# SwitchingRegulator.net
KiCad netlist of a schematic drawn in Altium Designer
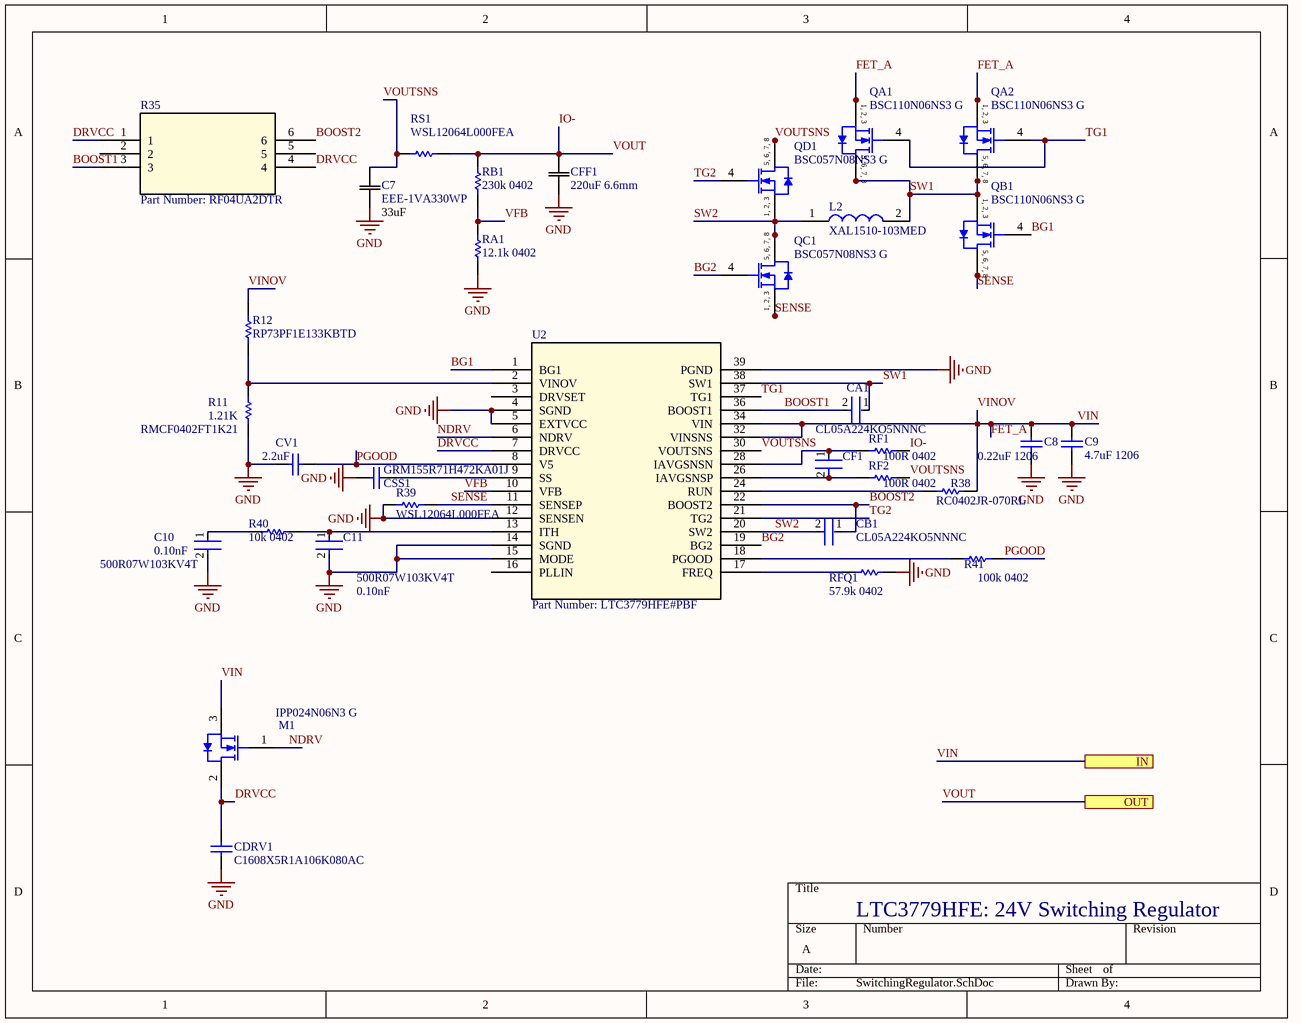
[diagram p0: SwitchingRegulator.SchDoc]

(export (version "E")
  (design (tool "Eeschema 10.0.6"))
  (components
    (comp (ref "C7")
      (value "EEE-1VA330WP")
      (footprint "CAPAE660X800N")
      (description "CAP ALUM 33UF 20% 35V SMD")
      (fields (field (name "ALTIUM_VALUE") "33uF"))
      (libsource (lib "2020-05-16_18-26-28") (part "UCV1V221MCL1GS"))
    )
    (comp (ref "C8")
      (value "0.22uF 1206")
      (footprint "CAPC1608X90X35ML10T15")
      (description "Chip Capacitor, 10 nF, +/- 10%, 50 V, -55 to 125 degC, 0603 (1608 Metric), RoHS, Tape and Reel")
      (fields (field (name "VOLTAGE") "50V") (field (name "TOLERANCE") "10%"))
      (libsource (lib "Altium Content Vault") (part "CAP-NP-2"))
    )
    (comp (ref "C9")
      (value "4.7uF 1206")
      (footprint "CAPC3216X180X50ML20T25")
      (description "Chip Capacitor, 1 uF, +/- 10%, 25 V, -55 to 125 degC, 1206 (3216 Metric), RoHS, Tape and Reel")
      (fields (field (name "MANUFACTURER") "Kemet") (field (name "TOLERANCE") "10%"))
      (libsource (lib "Altium Content Vault") (part "CAP-NP-2"))
    )
    (comp (ref "C10")
      (value "500R07W103KV4T")
      (footprint "FP-GRM15-MFG")
      (description "CAP CER 0.1UF 16V X7R 0402")
      (fields
        (field (name "MANUFACTURER PART NUMBER") "GRM155R71C104KA88D")
        (field (name "TOLERANCE") "10%")
        (field (name "CAPACITANCE") "0.10nF")
      )
      (libsource (lib "Altium Content Vault") (part "236180d848d6139a670b325ea6854c9"))
    )
    (comp (ref "C11")
      (value "500R07W103KV4T")
      (footprint "FP-GRM15-MFG")
      (description "CAP CER 0.1UF 16V X7R 0402")
      (fields
        (field (name "MANUFACTURER PART NUMBER") "GRM155R71C104KA88D")
        (field (name "TOLERANCE") "10%")
        (field (name "CAPACITANCE") "0.10nF")
      )
      (libsource (lib "Altium Content Vault") (part "236180d848d6139a670b325ea6854c9"))
    )
    (comp (ref "CA1")
      (value "CL05A224KO5NNNC")
      (footprint "FP-GRM15-MFG")
      (description "CAP CER 0.22UF 16V X5R 0402")
      (libsource (lib "Miscellaneous Devices") (part "236180d848d6139a670b325ea6854c9"))
    )
    (comp (ref "CB1")
      (value "CL05A224KO5NNNC")
      (footprint "FP-GRM15-MFG")
      (description "CAP CER 0.22UF 16V X5R 0402")
      (libsource (lib "Miscellaneous Devices") (part "236180d848d6139a670b325ea6854c9"))
    )
    (comp (ref "CDRV1")
      (value "C1608X5R1A106K080AC")
      (footprint "CAPC1608X90X20ML10")
      (description "Chip Capacitor, 10 uF, +/- 10%, 10 V, -55 to 85 degC, 0603 (1608 Metric), RoHS, Tape and Reel")
      (fields
        (field (name "PCN PART NUMBER") "MLCCPartNumberChange30/Nov/2012")
        (field (name "TOLERANCE") "±10%")
      )
      (libsource (lib "Altium Content Vault") (part "CAP-NP-2"))
    )
    (comp (ref "CF1")
      (value "C1608X5R1C335K080AC")
      (footprint "FP-GRM15-MFG")
      (description "CAP CER 3.3UF 16V X5R 0603")
      (libsource (lib "Miscellaneous Devices") (part "236180d848d6139a670b325ea6854c9"))
    )
    (comp (ref "CFF1")
      (value "220uF 6.6mm")
      (footprint "CAPAE660X800N")
      (description "No Description Available")
      (fields
        (field (name "MANUFACTURER_PART_NUMBER") "UCV1V221MCL1GS")
        (field (name "COPYRIGHT") "Copyright (C) 2018 Accelerated Designs. All rights reserved")
      )
      (libsource (lib "2020-05-16_18-26-28") (part "UCV1V221MCL1GS"))
    )
    (comp (ref "CSS1")
      (value "GRM155R71H472KA01J")
      (footprint "CAPC1005X55X25NL05T10")
      (description "CAP CER 4700PF 50V X7R 0402")
      (libsource (lib "Miscellaneous Devices") (part "CAP"))
    )
    (comp (ref "CV1")
      (value "2.2uF")
      (footprint "CAPC1005X55X25ML05T10")
      (description "CAP CER 2.2UF 6.3V X5R 0402")
      (fields (field (name "Comment") "GRM155R60J225ME15D"))
      (libsource (lib "Miscellaneous Devices") (part "CAP"))
    )
    (comp (ref "L2")
      (value "XAL1510-103MED")
      (footprint "PDB_footprints:XAL1513153MEB")
      (description "Inductor")
      (fields (field (name "MOUSER PART NUMBER") "994-XAL1510-103MED"))
      (libsource (lib "*") (part "XAL1510-103MED"))
    )
    (comp (ref "M1")
      (value "IPP024N06N3 G")
      (footprint "INF-PG-TO220-3-1_A_V")
      (fields (field (name "MANUFACTURER") "Infineon"))
      (libsource (lib "Altium Content Vault") (part "INF-NEMOS-GDS-3"))
    )
    (comp (ref "QA1")
      (value "BSC110N06NS3 G")
      (footprint "INF-PG-TDSON-8-1_V")
      (fields (field (name "MANUFACTURER") "Infineon"))
      (libsource (lib "Altium Content Vault") (part "INF-NEMOS-SSSGDDDD-8"))
    )
    (comp (ref "QA2")
      (value "BSC110N06NS3 G")
      (footprint "INF-PG-TDSON-8-1_V")
      (fields (field (name "MANUFACTURER") "Infineon"))
      (libsource (lib "Altium Content Vault") (part "INF-NEMOS-SSSGDDDD-8"))
    )
    (comp (ref "QB1")
      (value "BSC110N06NS3 G")
      (footprint "INF-PG-TDSON-8-1_V")
      (fields (field (name "MANUFACTURER") "Infineon"))
      (libsource (lib "Altium Content Vault") (part "INF-NEMOS-SSSGDDDD-8"))
    )
    (comp (ref "QC1")
      (value "BSC057N08NS3 G")
      (footprint "INF-PG-TDSON-8-1_V")
      (fields (field (name "MANUFACTURER") "Infineon"))
      (libsource (lib "Altium Content Vault") (part "INF-NEMOS-SSSGDDDD-8"))
    )
    (comp (ref "QD1")
      (value "BSC057N08NS3 G")
      (footprint "INF-PG-TDSON-8-1_V")
      (fields (field (name "MANUFACTURER") "Infineon"))
      (libsource (lib "Altium Content Vault") (part "INF-NEMOS-SSSGDDDD-8"))
    )
    (comp (ref "R11")
      (value "RMCF0402FT1K21")
      (footprint "RESC1005X40X25NL05T10")
      (description "RES 1.21K OHM 1% 1/16W 0402")
      (fields
        (field (name "MANUFACTURER") "Yageo / Phycomp")
        (field (name "PART NUMBER") "RC0402JR-070RL")
        (field (name "ALTIUM_VALUE") "1.21K")
      )
      (libsource (lib "Altium Content Vault") (part "RES"))
    )
    (comp (ref "R12")
      (value "RP73PF1E133KBTD")
      (footprint "RESC1005X40X25NL05T10")
      (description "RES 133K OHM 0.1% 1/10W 0402")
      (libsource (lib "Miscellaneous Devices") (part "RES"))
    )
    (comp (ref "R35")
      (value "Part Number: RF04UA2DTR")
      (footprint "RF04")
      (description "No Description Available")
      (fields
        (field (name "MANUFACTURER_PART_NUMBER") "RF04UA2DTR")
        (field (name "COPYRIGHT") "Copyright (C) 2018 Accelerated Designs. All rights reserved")
      )
      (libsource (lib "2020-05-23_22-38-39") (part "RF04UA2DTR"))
    )
    (comp (ref "R38")
      (value "RC0402JR-070RL")
      (footprint "RESC1005X40X25NL05T10")
      (fields (field (name "MANUFACTURER") "Yageo / Phycomp"))
      (libsource (lib "Altium Content Vault") (part "RES"))
    )
    (comp (ref "R39")
      (value "WSL12064L000FEA")
      (footprint "RESC3216X89X51LL25T25")
      (description "RES SMD 4mR 1% 1/8W 1206")
      (libsource (lib "Miscellaneous Devices") (part "RES"))
    )
    (comp (ref "R40")
      (value "10k 0402")
      (footprint "RESC1005X40X25NL05T10")
      (fields (field (name "MANUFACTURER") "Yageo / Phycomp") (field (name "PART NUMBER") "RC0402JR-070RL"))
      (libsource (lib "Altium Content Vault") (part "RES"))
    )
    (comp (ref "R41")
      (value "100k 0402")
      (footprint "RESC1005X40X25NL05T10")
      (fields (field (name "MANUFACTURER") "Yageo / Phycomp") (field (name "PART NUMBER") "RC0402JR-070RL"))
      (libsource (lib "Altium Content Vault") (part "RES"))
    )
    (comp (ref "RA1")
      (value "12.1k 0402")
      (footprint "RESC1005X40X25NL05T10")
      (fields (field (name "MANUFACTURER") "Yageo / Phycomp") (field (name "PART NUMBER") "RC0402JR-070RL"))
      (libsource (lib "Altium Content Vault") (part "RES"))
    )
    (comp (ref "RB1")
      (value "230k 0402")
      (footprint "RESC1005X40X25NL05T10")
      (fields (field (name "MANUFACTURER") "Yageo / Phycomp") (field (name "PART NUMBER") "RC0402JR-070RL"))
      (libsource (lib "Altium Content Vault") (part "RES"))
    )
    (comp (ref "RF1")
      (value "100R 0402")
      (footprint "RESC1005X40X25NL05T05")
      (fields (field (name "PART NUMBER") "CRCW0402100RFKED") (field (name "MANUFACTURER") "Vishay Dale"))
      (libsource (lib "Altium Content Vault") (part "RES"))
    )
    (comp (ref "RF2")
      (value "100R 0402")
      (footprint "RESC1005X40X25NL05T05")
      (fields (field (name "PART NUMBER") "CRCW0402100RFKED") (field (name "MANUFACTURER") "Vishay Dale"))
      (libsource (lib "Altium Content Vault") (part "RES"))
    )
    (comp (ref "RFQ1")
      (value "57.9k 0402")
      (footprint "RESC1005X40X25NL05T10")
      (fields (field (name "MANUFACTURER") "Yageo / Phycomp") (field (name "PART NUMBER") "RC0402JR-070RL"))
      (libsource (lib "Altium Content Vault") (part "RES"))
    )
    (comp (ref "RS1")
      (value "WSL12064L000FEA")
      (footprint "RESC3216X89X51LL25T25")
      (description "RES SMD 4mR 1% 1/8W 1206")
      (libsource (lib "Miscellaneous Devices") (part "RES"))
    )
    (comp (ref "U2")
      (value "Part Number: LTC3779HFE#PBF")
      (footprint "SOP50P640X120-39N")
      (description "No Description Available")
      (fields
        (field (name "MANUFACTURER_PART_NUMBER") "LTC3779HFE#PBF")
        (field (name "COPYRIGHT") "Copyright (C) 2016 Accelerated Designs. All rights reserved")
      )
      (libsource (lib "2020-05-16_19-22-25") (part "LTC3779HFE#PBF"))
    )
  )
  (nets
    (net (code "1") (name "/BG1") (class "Default")
      (node (ref "QB1") (pin "4") (pinfunction "GATE_4") (pintype "passive"))
      (node (ref "U2") (pin "1") (pinfunction "BG1_1") (pintype "passive"))
    )
    (net (code "2") (name "/BG2") (class "Default")
      (node (ref "QC1") (pin "4") (pinfunction "GATE_4") (pintype "passive"))
      (node (ref "U2") (pin "19") (pinfunction "BG2_19") (pintype "passive"))
    )
    (net (code "3") (name "/BOOST1") (class "Default")
      (node (ref "CA1") (pin "2") (pinfunction "2_2") (pintype "passive"))
      (node (ref "R35") (pin "3") (pinfunction "3_3") (pintype "passive"))
      (node (ref "U2") (pin "36") (pinfunction "BOOST1_36") (pintype "passive"))
    )
    (net (code "4") (name "/BOOST2") (class "Default")
      (node (ref "CB1") (pin "1") (pinfunction "1_1") (pintype "passive"))
      (node (ref "R35") (pin "6") (pinfunction "6_6") (pintype "passive"))
      (node (ref "U2") (pin "22") (pinfunction "BOOST2_22") (pintype "passive"))
    )
    (net (code "5") (name "/DRVCC") (class "Default")
      (node (ref "CDRV1") (pin "2") (pinfunction "2_2") (pintype "passive"))
      (node (ref "M1") (pin "2") (pinfunction "DRAIN_2") (pintype "passive"))
      (node (ref "R35") (pin "1") (pinfunction "1_1") (pintype "passive"))
      (node (ref "R35") (pin "4") (pinfunction "4_4") (pintype "passive"))
      (node (ref "U2") (pin "7") (pinfunction "DRVCC_7") (pintype "passive"))
    )
    (net (code "6") (name "/FET_A") (class "Default")
      (node (ref "C8") (pin "2") (pinfunction "2_2") (pintype "passive"))
      (node (ref "C9") (pin "2") (pinfunction "2_2") (pintype "passive"))
      (node (ref "M1") (pin "3") (pinfunction "SOURCE_3") (pintype "passive"))
      (node (ref "QA1") (pin "1") (pinfunction "SOURCE_1") (pintype "passive"))
      (node (ref "QA1") (pin "2") (pinfunction "SOURCE_2") (pintype "passive"))
      (node (ref "QA1") (pin "3") (pinfunction "SOURCE_3") (pintype "passive"))
      (node (ref "QA2") (pin "1") (pinfunction "SOURCE_1") (pintype "passive"))
      (node (ref "QA2") (pin "2") (pinfunction "SOURCE_2") (pintype "passive"))
      (node (ref "QA2") (pin "3") (pinfunction "SOURCE_3") (pintype "passive"))
      (node (ref "R12") (pin "1") (pinfunction "1_1") (pintype "passive"))
      (node (ref "R38") (pin "1") (pinfunction "1_1") (pintype "passive"))
      (node (ref "U2") (pin "32") (pinfunction "VINSNS_32") (pintype "passive"))
      (node (ref "U2") (pin "34") (pinfunction "VIN_34") (pintype "passive"))
    )
    (net (code "7") (name "/IO-") (class "Default")
      (node (ref "CFF1") (pin "2") (pinfunction "2_2") (pintype "passive"))
      (node (ref "RB1") (pin "2") (pinfunction "2_2") (pintype "passive"))
      (node (ref "RF1") (pin "2") (pinfunction "2_2") (pintype "passive"))
      (node (ref "RS1") (pin "2") (pinfunction "2_2") (pintype "passive"))
    )
    (net (code "8") (name "/NDRV") (class "Default")
      (node (ref "M1") (pin "1") (pinfunction "GATE_1") (pintype "passive"))
      (node (ref "U2") (pin "6") (pinfunction "NDRV_6") (pintype "passive"))
    )
    (net (code "9") (name "/PGOOD") (class "Default")
      (node (ref "CV1") (pin "2") (pinfunction "2_2") (pintype "passive"))
      (node (ref "R41") (pin "1") (pinfunction "1_1") (pintype "passive"))
      (node (ref "U2") (pin "8") (pinfunction "V5_8") (pintype "passive"))
    )
    (net (code "10") (name "/SENSE") (class "Default")
      (node (ref "QB1") (pin "5") (pinfunction "DRAIN_5") (pintype "passive"))
      (node (ref "QB1") (pin "6") (pinfunction "DRAIN_6") (pintype "passive"))
      (node (ref "QB1") (pin "7") (pinfunction "DRAIN_7") (pintype "passive"))
      (node (ref "QB1") (pin "8") (pinfunction "DRAIN_8") (pintype "passive"))
      (node (ref "QC1") (pin "1") (pinfunction "SOURCE_1") (pintype "passive"))
      (node (ref "QC1") (pin "2") (pinfunction "SOURCE_2") (pintype "passive"))
      (node (ref "QC1") (pin "3") (pinfunction "SOURCE_3") (pintype "passive"))
      (node (ref "R39") (pin "2") (pinfunction "2_2") (pintype "passive"))
      (node (ref "U2") (pin "11") (pinfunction "SENSEP_11") (pintype "passive"))
    )
    (net (code "11") (name "/SW1") (class "Default")
      (node (ref "CA1") (pin "1") (pinfunction "1_1") (pintype "passive"))
      (node (ref "L2") (pin "2") (pinfunction "2_2") (pintype "passive"))
      (node (ref "QA1") (pin "5") (pinfunction "DRAIN_5") (pintype "passive"))
      (node (ref "QA1") (pin "6") (pinfunction "DRAIN_6") (pintype "passive"))
      (node (ref "QA1") (pin "7") (pinfunction "DRAIN_7") (pintype "passive"))
      (node (ref "QA1") (pin "8") (pinfunction "DRAIN_8") (pintype "passive"))
      (node (ref "QA2") (pin "5") (pinfunction "DRAIN_5") (pintype "passive"))
      (node (ref "QA2") (pin "6") (pinfunction "DRAIN_6") (pintype "passive"))
      (node (ref "QA2") (pin "7") (pinfunction "DRAIN_7") (pintype "passive"))
      (node (ref "QA2") (pin "8") (pinfunction "DRAIN_8") (pintype "passive"))
      (node (ref "QB1") (pin "1") (pinfunction "SOURCE_1") (pintype "passive"))
      (node (ref "QB1") (pin "2") (pinfunction "SOURCE_2") (pintype "passive"))
      (node (ref "QB1") (pin "3") (pinfunction "SOURCE_3") (pintype "passive"))
      (node (ref "U2") (pin "38") (pinfunction "SW1_38") (pintype "passive"))
    )
    (net (code "12") (name "/SW2") (class "Default")
      (node (ref "CB1") (pin "2") (pinfunction "2_2") (pintype "passive"))
      (node (ref "L2") (pin "1") (pinfunction "1_1") (pintype "passive"))
      (node (ref "QC1") (pin "5") (pinfunction "DRAIN_5") (pintype "passive"))
      (node (ref "QC1") (pin "6") (pinfunction "DRAIN_6") (pintype "passive"))
      (node (ref "QC1") (pin "7") (pinfunction "DRAIN_7") (pintype "passive"))
      (node (ref "QC1") (pin "8") (pinfunction "DRAIN_8") (pintype "passive"))
      (node (ref "QD1") (pin "1") (pinfunction "SOURCE_1") (pintype "passive"))
      (node (ref "QD1") (pin "2") (pinfunction "SOURCE_2") (pintype "passive"))
      (node (ref "QD1") (pin "3") (pinfunction "SOURCE_3") (pintype "passive"))
      (node (ref "U2") (pin "20") (pinfunction "SW2_20") (pintype "passive"))
    )
    (net (code "13") (name "/TG1") (class "Default")
      (node (ref "QA1") (pin "4") (pinfunction "GATE_4") (pintype "passive"))
      (node (ref "QA2") (pin "4") (pinfunction "GATE_4") (pintype "passive"))
      (node (ref "U2") (pin "37") (pinfunction "TG1_37") (pintype "passive"))
    )
    (net (code "14") (name "/TG2") (class "Default")
      (node (ref "QD1") (pin "4") (pinfunction "GATE_4") (pintype "passive"))
      (node (ref "U2") (pin "21") (pinfunction "TG2_21") (pintype "passive"))
    )
    (net (code "15") (name "/VFB") (class "Default")
      (node (ref "RA1") (pin "2") (pinfunction "2_2") (pintype "passive"))
      (node (ref "RB1") (pin "1") (pinfunction "1_1") (pintype "passive"))
      (node (ref "U2") (pin "10") (pinfunction "VFB_10") (pintype "passive"))
    )
    (net (code "16") (name "/VOUTSNS") (class "Default")
      (node (ref "C7") (pin "2") (pinfunction "2_2") (pintype "passive"))
      (node (ref "QD1") (pin "5") (pinfunction "DRAIN_5") (pintype "passive"))
      (node (ref "QD1") (pin "6") (pinfunction "DRAIN_6") (pintype "passive"))
      (node (ref "QD1") (pin "7") (pinfunction "DRAIN_7") (pintype "passive"))
      (node (ref "QD1") (pin "8") (pinfunction "DRAIN_8") (pintype "passive"))
      (node (ref "RF2") (pin "2") (pinfunction "2_2") (pintype "passive"))
      (node (ref "RS1") (pin "1") (pinfunction "1_1") (pintype "passive"))
      (node (ref "U2") (pin "30") (pinfunction "VOUTSNS_30") (pintype "passive"))
    )
    (net (code "17") (name "GND") (class "Default")
      (node (ref "C10") (pin "2") (pinfunction "2_2") (pintype "passive"))
      (node (ref "C11") (pin "2") (pinfunction "2_2") (pintype "passive"))
      (node (ref "C7") (pin "1") (pinfunction "1_1") (pintype "passive"))
      (node (ref "C8") (pin "1") (pinfunction "1_1") (pintype "passive"))
      (node (ref "C9") (pin "1") (pinfunction "1_1") (pintype "passive"))
      (node (ref "CDRV1") (pin "1") (pinfunction "1_1") (pintype "passive"))
      (node (ref "CFF1") (pin "1") (pinfunction "1_1") (pintype "passive"))
      (node (ref "CSS1") (pin "1") (pinfunction "1_1") (pintype "passive"))
      (node (ref "CV1") (pin "1") (pinfunction "1_1") (pintype "passive"))
      (node (ref "R11") (pin "2") (pinfunction "2_2") (pintype "passive"))
      (node (ref "R39") (pin "1") (pinfunction "1_1") (pintype "passive"))
      (node (ref "RA1") (pin "1") (pinfunction "1_1") (pintype "passive"))
      (node (ref "RFQ1") (pin "1") (pinfunction "1_1") (pintype "passive"))
      (node (ref "U2") (pin "12") (pinfunction "SENSEN_12") (pintype "passive"))
      (node (ref "U2") (pin "14") (pinfunction "SGND_14") (pintype "passive"))
      (node (ref "U2") (pin "15") (pinfunction "MODE_15") (pintype "passive"))
      (node (ref "U2") (pin "39") (pinfunction "PGND_39") (pintype "passive"))
      (node (ref "U2") (pin "4") (pinfunction "SGND_4") (pintype "passive"))
      (node (ref "U2") (pin "5") (pinfunction "EXTVCC_5") (pintype "passive"))
    )
    (net (code "18") (name "Net-(C10-Pad1)") (class "Default")
      (node (ref "C10") (pin "1") (pinfunction "1_1") (pintype "passive"))
      (node (ref "R40") (pin "2") (pinfunction "2_2") (pintype "passive"))
    )
    (net (code "19") (name "Net-(U2-FREQ)") (class "Default")
      (node (ref "RFQ1") (pin "2") (pinfunction "2_2") (pintype "passive"))
      (node (ref "U2") (pin "17") (pinfunction "FREQ_17") (pintype "passive"))
    )
    (net (code "20") (name "Net-(U2-IAVGSNSN)") (class "Default")
      (node (ref "CF1") (pin "1") (pinfunction "1_1") (pintype "passive"))
      (node (ref "RF1") (pin "1") (pinfunction "1_1") (pintype "passive"))
      (node (ref "U2") (pin "28") (pinfunction "IAVGSNSN_28") (pintype "passive"))
    )
    (net (code "21") (name "Net-(U2-IAVGSNSP)") (class "Default")
      (node (ref "CF1") (pin "2") (pinfunction "2_2") (pintype "passive"))
      (node (ref "RF2") (pin "1") (pinfunction "1_1") (pintype "passive"))
      (node (ref "U2") (pin "26") (pinfunction "IAVGSNSP_26") (pintype "passive"))
    )
    (net (code "22") (name "Net-(U2-ITH)") (class "Default")
      (node (ref "C11") (pin "1") (pinfunction "1_1") (pintype "passive"))
      (node (ref "R40") (pin "1") (pinfunction "1_1") (pintype "passive"))
      (node (ref "U2") (pin "13") (pinfunction "ITH_13") (pintype "passive"))
    )
    (net (code "23") (name "Net-(U2-PGOOD)") (class "Default")
      (node (ref "R41") (pin "2") (pinfunction "2_2") (pintype "passive"))
      (node (ref "U2") (pin "18") (pinfunction "PGOOD_18") (pintype "passive"))
    )
    (net (code "24") (name "Net-(U2-RUN)") (class "Default")
      (node (ref "R38") (pin "2") (pinfunction "2_2") (pintype "passive"))
      (node (ref "U2") (pin "24") (pinfunction "RUN_24") (pintype "passive"))
    )
    (net (code "25") (name "Net-(U2-SS)") (class "Default")
      (node (ref "CSS1") (pin "2") (pinfunction "2_2") (pintype "passive"))
      (node (ref "U2") (pin "9") (pinfunction "SS_9") (pintype "passive"))
    )
    (net (code "26") (name "Net-(U2-VINOV)") (class "Default")
      (node (ref "R11") (pin "1") (pinfunction "1_1") (pintype "passive"))
      (node (ref "R12") (pin "2") (pinfunction "2_2") (pintype "passive"))
      (node (ref "U2") (pin "2") (pinfunction "VINOV_2") (pintype "passive"))
    )
    (net (code "27") (name "unconnected-(R35-Pad2)") (class "Default")
      (node (ref "R35") (pin "2") (pinfunction "2_2") (pintype "passive"))
    )
    (net (code "28") (name "unconnected-(R35-Pad5)") (class "Default")
      (node (ref "R35") (pin "5") (pinfunction "5_5") (pintype "passive"))
    )
    (net (code "29") (name "unconnected-(U2-DRVSET-Pad3)") (class "Default")
      (node (ref "U2") (pin "3") (pinfunction "DRVSET_3") (pintype "passive"))
    )
    (net (code "30") (name "unconnected-(U2-PLLIN-Pad16)") (class "Default")
      (node (ref "U2") (pin "16") (pinfunction "PLLIN_16") (pintype "passive"))
    )
  )
)
